# 07-General_I2C_Devices.net
KiCad netlist of a schematic drawn in Altium Designer
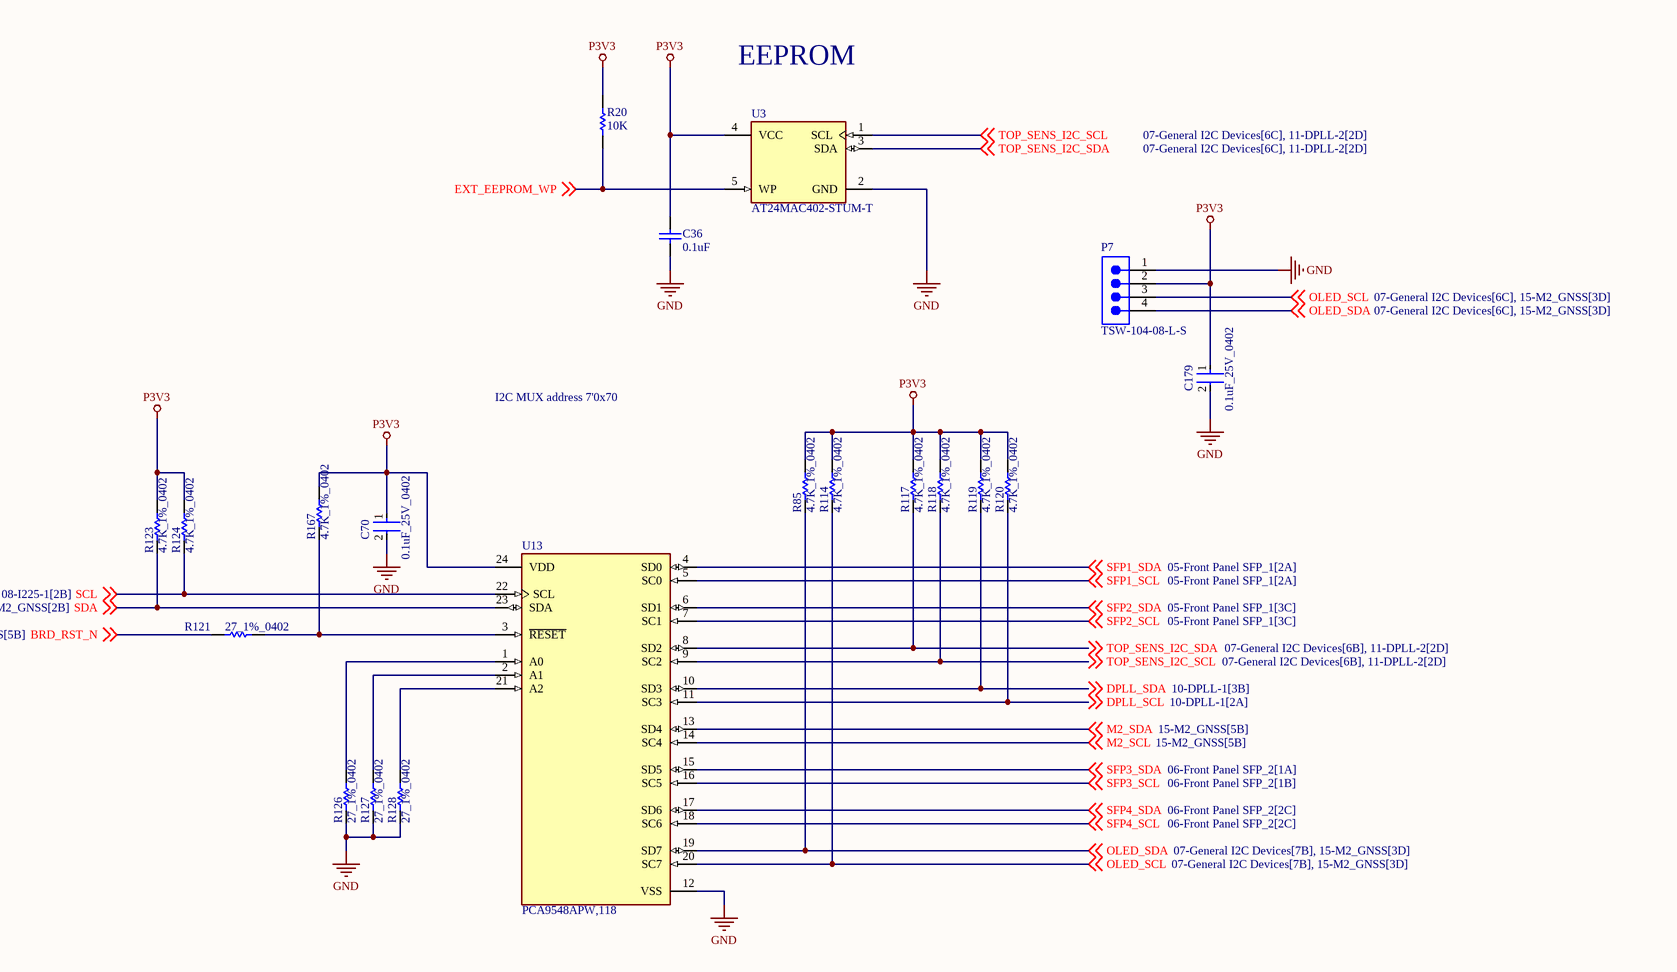
[diagram p0: 07-General I2C Devices.SchDoc]

(export (version "E")
  (design (tool "Eeschema 10.0.6"))
  (components
    (comp (ref "C36")
      (value "0.1uF")
      (footprint "CAPC1608X87X45ML20T05")
      (description "C0603X104K5RACAUTO")
      (fields (field (name "MANUFACTURER") "Kemet"))
      (libsource (lib "Altium Content Vault") (part "CAP"))
    )
    (comp (ref "C70")
      (value "0.1uF_25V_0402")
      (footprint "FP-0402-L_1_0_1-W_0_5_0_1-IPC_C")
      (description "General Purpose Ceramic Capacitor, 0402, 100nF, 10%, X7R, 15%, 25V")
      (fields (field (name "VOLTAGE") "25V") (field (name "TOLERANCE") "10%"))
      (libsource (lib "Altium Content Vault") (part "b4654b650e69147ec39a6b967a45e02"))
    )
    (comp (ref "C179")
      (value "0.1uF_25V_0402")
      (footprint "FP-0402-L_1_0_1-W_0_5_0_1-IPC_C")
      (description "General Purpose Ceramic Capacitor, 0402, 100nF, 10%, X7R, 15%, 25V")
      (fields (field (name "VOLTAGE") "25V") (field (name "TOLERANCE") "10%"))
      (libsource (lib "Altium Content Vault") (part "b4654b650e69147ec39a6b967a45e02"))
    )
    (comp (ref "P7")
      (value "TSW-104-08-L-S")
      (footprint "SMTC-TSW-104-08-X-S")
      (description "0.025\" SQ Post Header, Through-hole, Vertical, -55 to 125 degC, 2.54 mm Pitch, 4-Pin, Male, RoHS")
      (fields (field (name "MANUFACTURER") "Samtec"))
      (libsource (lib "Altium Content Vault") (part "SMTC-TSW-104-08-X-S"))
    )
    (comp (ref "R20")
      (value "10K")
      (footprint "RESC1608X55X30LL15T20")
      (fields (field (name "TOLERANCE") "±1%") (field (name "MANUFACTURER") "Stackpole-Electronics-Inc."))
      (libsource (lib "Altium Content Vault") (part "RES-2"))
    )
    (comp (ref "R85")
      (value "4.7K_1%_0402")
      (footprint "RESC1005X40X25NL10T10")
      (fields (field (name "MANUFACTURER") "Bourns") (field (name "PART NUMBER") "CR0402-FX-4701GLF"))
      (libsource (lib "Altium Content Vault") (part "RES"))
    )
    (comp (ref "R114")
      (value "4.7K_1%_0402")
      (footprint "RESC1005X40X25NL10T10")
      (fields (field (name "MANUFACTURER") "Bourns") (field (name "PART NUMBER") "CR0402-FX-4701GLF"))
      (libsource (lib "Altium Content Vault") (part "RES"))
    )
    (comp (ref "R117")
      (value "4.7K_1%_0402")
      (footprint "RESC1005X40X25NL10T10")
      (fields (field (name "MANUFACTURER") "Bourns") (field (name "PART NUMBER") "CR0402-FX-4701GLF"))
      (libsource (lib "Altium Content Vault") (part "RES"))
    )
    (comp (ref "R118")
      (value "4.7K_1%_0402")
      (footprint "RESC1005X40X25NL10T10")
      (fields (field (name "MANUFACTURER") "Bourns") (field (name "PART NUMBER") "CR0402-FX-4701GLF"))
      (libsource (lib "Altium Content Vault") (part "RES"))
    )
    (comp (ref "R119")
      (value "4.7K_1%_0402")
      (footprint "RESC1005X40X25NL10T10")
      (fields (field (name "MANUFACTURER") "Bourns") (field (name "PART NUMBER") "CR0402-FX-4701GLF"))
      (libsource (lib "Altium Content Vault") (part "RES"))
    )
    (comp (ref "R120")
      (value "4.7K_1%_0402")
      (footprint "RESC1005X40X25NL10T10")
      (fields (field (name "MANUFACTURER") "Bourns") (field (name "PART NUMBER") "CR0402-FX-4701GLF"))
      (libsource (lib "Altium Content Vault") (part "RES"))
    )
    (comp (ref "R121")
      (value "27_1%_0402")
      (footprint "RESC1005X40X25NL05T05")
      (fields (field (name "PART NUMBER") "CRCW040227R0FKED") (field (name "MANUFACTURER") "Vishay Dale"))
      (libsource (lib "Altium Content Vault") (part "RES"))
    )
    (comp (ref "R123")
      (value "4.7K_1%_0402")
      (footprint "RESC1005X40X25NL10T10")
      (fields (field (name "MANUFACTURER") "Bourns") (field (name "PART NUMBER") "CR0402-FX-4701GLF"))
      (libsource (lib "Altium Content Vault") (part "RES"))
    )
    (comp (ref "R124")
      (value "4.7K_1%_0402")
      (footprint "RESC1005X40X25NL10T10")
      (fields (field (name "MANUFACTURER") "Bourns") (field (name "PART NUMBER") "CR0402-FX-4701GLF"))
      (libsource (lib "Altium Content Vault") (part "RES"))
    )
    (comp (ref "R126")
      (value "27_1%_0402")
      (footprint "RESC1005X40X25NL05T05")
      (fields (field (name "PART NUMBER") "CRCW040227R0FKED") (field (name "MANUFACTURER") "Vishay Dale"))
      (libsource (lib "Altium Content Vault") (part "RES"))
    )
    (comp (ref "R127")
      (value "27_1%_0402")
      (footprint "RESC1005X40X25NL05T05")
      (fields (field (name "PART NUMBER") "CRCW040227R0FKED") (field (name "MANUFACTURER") "Vishay Dale"))
      (libsource (lib "Altium Content Vault") (part "RES"))
    )
    (comp (ref "R128")
      (value "27_1%_0402")
      (footprint "RESC1005X40X25NL05T05")
      (fields (field (name "PART NUMBER") "CRCW040227R0FKED") (field (name "MANUFACTURER") "Vishay Dale"))
      (libsource (lib "Altium Content Vault") (part "RES"))
    )
    (comp (ref "R167")
      (value "4.7K_1%_0402")
      (footprint "RESC1005X40X25NL10T10")
      (fields (field (name "MANUFACTURER") "Bourns") (field (name "PART NUMBER") "CR0402-FX-4701GLF"))
      (libsource (lib "Altium Content Vault") (part "RES"))
    )
    (comp (ref "U3")
      (value "AT24MAC402-STUM-T")
      (footprint "FP-5TS1-IPC_C")
      (description "IC EEPROM 2K I2C 1MHZ SOT23-5")
      (fields
        (field (name "MANUFACTURER") "Microchip")
        (field (name "OCTOPART") "https://octopart.com/at24mac402-stum-t-microchip-77758112")
      )
      (libsource (lib "Altium Content Vault") (part "93fe34f5f049140596bab6421a6454b"))
    )
    (comp (ref "U13")
      (value "PCA9548APW,118")
      (footprint "FP-SOT355-1-MFG")
      (description "IC INTERFACE SPECIALIZED 24TSSOP")
      (libsource (lib "Altium Content Vault") (part "3e168d29e2cae1e9eb34f21911d2ccb"))
    )
  )
  (nets
    (net (code "1") (name "BRD_RST_N") (class "Default")
      (node (ref "R121") (pin "1") (pinfunction "1_1") (pintype "passive"))
    )
    (net (code "2") (name "DPLL_SCL") (class "Default")
      (node (ref "R120") (pin "1") (pinfunction "1_1") (pintype "passive"))
      (node (ref "U13") (pin "11") (pinfunction "SC3_11") (pintype "input"))
    )
    (net (code "3") (name "DPLL_SDA") (class "Default")
      (node (ref "R119") (pin "1") (pinfunction "1_1") (pintype "passive"))
      (node (ref "U13") (pin "10") (pinfunction "SD3_10") (pintype "bidirectional"))
    )
    (net (code "4") (name "EXT_EEPROM_WP") (class "Default")
      (node (ref "R20") (pin "1") (pinfunction "1_1") (pintype "passive"))
      (node (ref "U3") (pin "5") (pinfunction "WP_5") (pintype "input"))
    )
    (net (code "5") (name "GND") (class "Default")
      (node (ref "C179") (pin "2") (pinfunction "2_2") (pintype "passive"))
      (node (ref "C36") (pin "1") (pinfunction "1_1") (pintype "passive"))
      (node (ref "C70") (pin "2") (pinfunction "2_2") (pintype "passive"))
      (node (ref "P7") (pin "1") (pinfunction "1_1") (pintype "passive"))
      (node (ref "R126") (pin "1") (pinfunction "1_1") (pintype "passive"))
      (node (ref "R127") (pin "1") (pinfunction "1_1") (pintype "passive"))
      (node (ref "R128") (pin "1") (pinfunction "1_1") (pintype "passive"))
      (node (ref "U13") (pin "12") (pinfunction "VSS_12") (pintype "power_in"))
      (node (ref "U3") (pin "2") (pinfunction "GND_2") (pintype "power_in"))
    )
    (net (code "6") (name "M2_SCL") (class "Default")
      (node (ref "U13") (pin "14") (pinfunction "SC4_14") (pintype "input"))
    )
    (net (code "7") (name "M2_SDA") (class "Default")
      (node (ref "U13") (pin "13") (pinfunction "SD4_13") (pintype "bidirectional"))
    )
    (net (code "8") (name "Net-(U13-A0)") (class "Default")
      (node (ref "R126") (pin "2") (pinfunction "2_2") (pintype "passive"))
      (node (ref "U13") (pin "1") (pinfunction "A0_1") (pintype "input"))
    )
    (net (code "9") (name "Net-(U13-A1)") (class "Default")
      (node (ref "R127") (pin "2") (pinfunction "2_2") (pintype "passive"))
      (node (ref "U13") (pin "2") (pinfunction "A1_2") (pintype "input"))
    )
    (net (code "10") (name "Net-(U13-A2)") (class "Default")
      (node (ref "R128") (pin "2") (pinfunction "2_2") (pintype "passive"))
      (node (ref "U13") (pin "21") (pinfunction "A2_21") (pintype "input"))
    )
    (net (code "11") (name "Net-(U13-~{RESET})") (class "Default")
      (node (ref "R121") (pin "2") (pinfunction "2_2") (pintype "passive"))
      (node (ref "R167") (pin "1") (pinfunction "1_1") (pintype "passive"))
      (node (ref "U13") (pin "3") (pinfunction "~{RESET}_3") (pintype "input"))
    )
    (net (code "12") (name "OLED_SCL") (class "Default")
      (node (ref "P7") (pin "3") (pinfunction "3_3") (pintype "passive"))
      (node (ref "R114") (pin "1") (pinfunction "1_1") (pintype "passive"))
      (node (ref "U13") (pin "20") (pinfunction "SC7_20") (pintype "input"))
    )
    (net (code "13") (name "OLED_SDA") (class "Default")
      (node (ref "P7") (pin "4") (pinfunction "4_4") (pintype "passive"))
      (node (ref "R85") (pin "1") (pinfunction "1_1") (pintype "passive"))
      (node (ref "U13") (pin "19") (pinfunction "SD7_19") (pintype "bidirectional"))
    )
    (net (code "14") (name "P3V3") (class "Default")
      (node (ref "C179") (pin "1") (pinfunction "1_1") (pintype "passive"))
      (node (ref "C36") (pin "2") (pinfunction "2_2") (pintype "passive"))
      (node (ref "C70") (pin "1") (pinfunction "1_1") (pintype "passive"))
      (node (ref "P7") (pin "2") (pinfunction "2_2") (pintype "passive"))
      (node (ref "R114") (pin "2") (pinfunction "2_2") (pintype "passive"))
      (node (ref "R117") (pin "2") (pinfunction "2_2") (pintype "passive"))
      (node (ref "R118") (pin "2") (pinfunction "2_2") (pintype "passive"))
      (node (ref "R119") (pin "2") (pinfunction "2_2") (pintype "passive"))
      (node (ref "R120") (pin "2") (pinfunction "2_2") (pintype "passive"))
      (node (ref "R123") (pin "2") (pinfunction "2_2") (pintype "passive"))
      (node (ref "R124") (pin "2") (pinfunction "2_2") (pintype "passive"))
      (node (ref "R167") (pin "2") (pinfunction "2_2") (pintype "passive"))
      (node (ref "R20") (pin "2") (pinfunction "2_2") (pintype "passive"))
      (node (ref "R85") (pin "2") (pinfunction "2_2") (pintype "passive"))
      (node (ref "U13") (pin "24") (pinfunction "VDD_24") (pintype "power_in"))
      (node (ref "U3") (pin "4") (pinfunction "VCC_4") (pintype "power_in"))
    )
    (net (code "15") (name "SCL") (class "Default")
      (node (ref "R124") (pin "1") (pinfunction "1_1") (pintype "passive"))
      (node (ref "U13") (pin "22") (pinfunction "SCL_22") (pintype "input"))
    )
    (net (code "16") (name "SDA") (class "Default")
      (node (ref "R123") (pin "1") (pinfunction "1_1") (pintype "passive"))
      (node (ref "U13") (pin "23") (pinfunction "SDA_23") (pintype "bidirectional"))
    )
    (net (code "17") (name "SFP1_SCL") (class "Default")
      (node (ref "U13") (pin "5") (pinfunction "SC0_5") (pintype "input"))
    )
    (net (code "18") (name "SFP1_SDA") (class "Default")
      (node (ref "U13") (pin "4") (pinfunction "SD0_4") (pintype "bidirectional"))
    )
    (net (code "19") (name "SFP2_SCL") (class "Default")
      (node (ref "U13") (pin "7") (pinfunction "SC1_7") (pintype "input"))
    )
    (net (code "20") (name "SFP2_SDA") (class "Default")
      (node (ref "U13") (pin "6") (pinfunction "SD1_6") (pintype "bidirectional"))
    )
    (net (code "21") (name "SFP3_SCL") (class "Default")
      (node (ref "U13") (pin "16") (pinfunction "SC5_16") (pintype "input"))
    )
    (net (code "22") (name "SFP3_SDA") (class "Default")
      (node (ref "U13") (pin "15") (pinfunction "SD5_15") (pintype "bidirectional"))
    )
    (net (code "23") (name "SFP4_SCL") (class "Default")
      (node (ref "U13") (pin "18") (pinfunction "SC6_18") (pintype "input"))
    )
    (net (code "24") (name "SFP4_SDA") (class "Default")
      (node (ref "U13") (pin "17") (pinfunction "SD6_17") (pintype "bidirectional"))
    )
    (net (code "25") (name "TOP_SENS_I2C_SCL") (class "Default")
      (node (ref "R118") (pin "1") (pinfunction "1_1") (pintype "passive"))
      (node (ref "U13") (pin "9") (pinfunction "SC2_9") (pintype "input"))
      (node (ref "U3") (pin "1") (pinfunction "SCL_1") (pintype "input"))
    )
    (net (code "26") (name "TOP_SENS_I2C_SDA") (class "Default")
      (node (ref "R117") (pin "1") (pinfunction "1_1") (pintype "passive"))
      (node (ref "U13") (pin "8") (pinfunction "SD2_8") (pintype "bidirectional"))
      (node (ref "U3") (pin "3") (pinfunction "SDA_3") (pintype "bidirectional"))
    )
  )
)
